# Astabile_Base.net
KiCad netlist of a schematic drawn in EAGLE
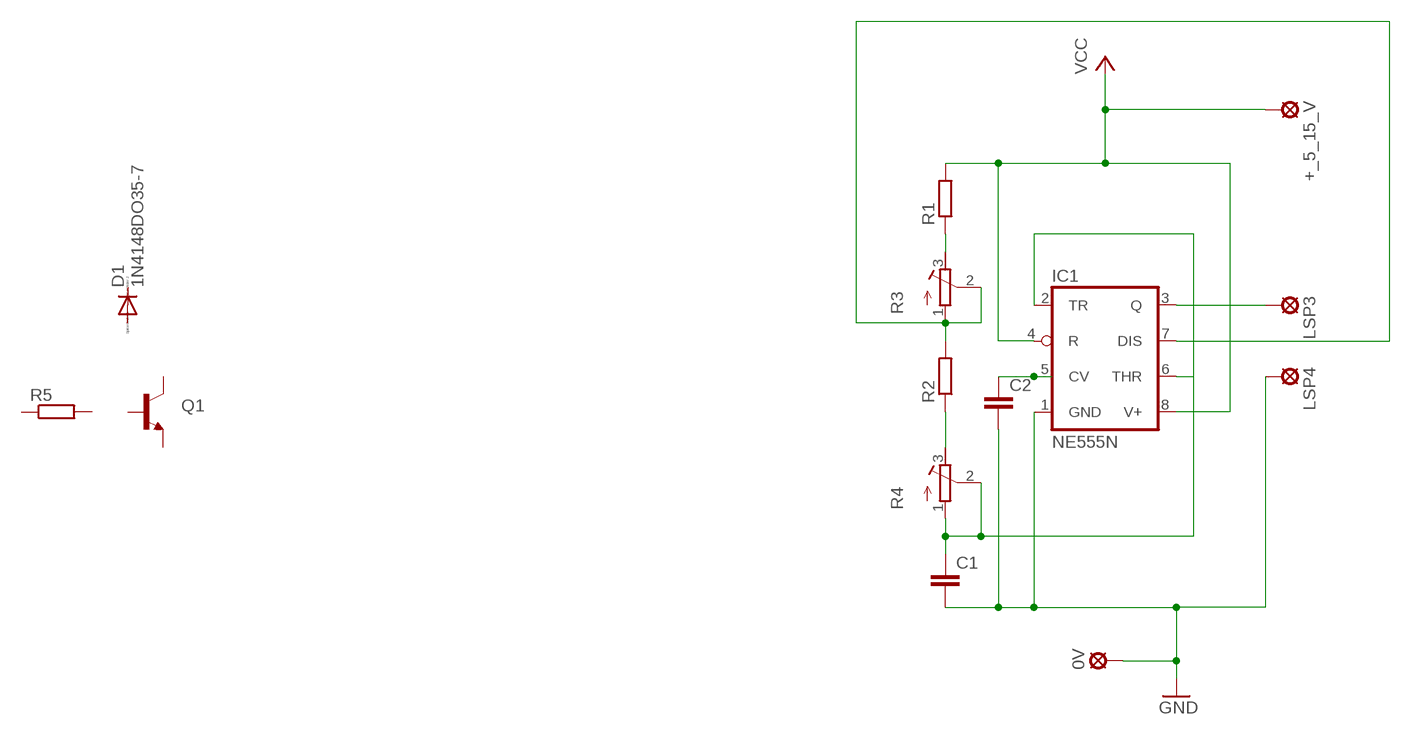
[diagram p0: schematic, sheet 1]

(export (version "E")
  (design (tool "Eeschema 10.0.6"))
  (components
    (comp (ref "+_5_15_V")
      (value "LSP10")
      (footprint "eagle-import:LSP10")
      (libsource (lib "eagle-import") (part "LSP10"))
    )
    (comp (ref "0V")
      (value "LSP10")
      (footprint "eagle-import:LSP10")
      (libsource (lib "eagle-import") (part "LSP10"))
    )
    (comp (ref "C1")
      (value "C-EU050-024X044")
      (footprint "eagle-import:C050-024X044")
      (libsource (lib "eagle-import") (part "C-EU050-024X044"))
    )
    (comp (ref "C2")
      (value "C-EU050-024X044")
      (footprint "eagle-import:C050-024X044")
      (libsource (lib "eagle-import") (part "C-EU050-024X044"))
    )
    (comp (ref "D1")
      (value "1N4148DO35-7")
      (footprint "eagle-import:DO35-7")
      (libsource (lib "eagle-import") (part "1N4148DO35-7"))
    )
    (comp (ref "IC1")
      (value "NE555N")
      (footprint "eagle-import:DIL08")
      (libsource (lib "eagle-import") (part "555NNE"))
    )
    (comp (ref "LSP3")
      (value "LSP10")
      (footprint "eagle-import:LSP10")
      (libsource (lib "eagle-import") (part "LSP10"))
    )
    (comp (ref "LSP4")
      (value "LSP10")
      (footprint "eagle-import:LSP10")
      (libsource (lib "eagle-import") (part "LSP10"))
    )
    (comp (ref "Q1")
      (value "TRANSISTOR_NPNBC547")
      (footprint "eagle-import:TO-92-AMMO")
      (libsource (lib "eagle-import") (part "TRANSISTOR_NPNBC547"))
    )
    (comp (ref "R1")
      (value "R-EU_0204/7")
      (footprint "eagle-import:0204_7")
      (libsource (lib "eagle-import") (part "R-EU_0204/7"))
    )
    (comp (ref "R2")
      (value "R-EU_0204/7")
      (footprint "eagle-import:0204_7")
      (libsource (lib "eagle-import") (part "R-EU_0204/7"))
    )
    (comp (ref "R3")
      (value "R-TRIMM3339P")
      (footprint "eagle-import:RTRIM3339P")
      (libsource (lib "eagle-import") (part "R-TRIMM3339P"))
    )
    (comp (ref "R4")
      (value "R-TRIMM3339P")
      (footprint "eagle-import:RTRIM3339P")
      (libsource (lib "eagle-import") (part "R-TRIMM3339P"))
    )
    (comp (ref "R5")
      (value "R-EU_0207/2V")
      (footprint "eagle-import:0207_2V")
      (libsource (lib "eagle-import") (part "R-EU_0207/2V"))
    )
  )
  (nets
    (net (code "1") (name "GND") (class "Default")
      (node (ref "0V") (pin "MP") (pinfunction "MP_MP") (pintype "passive"))
      (node (ref "C1") (pin "2") (pinfunction "2_2") (pintype "passive"))
      (node (ref "C2") (pin "2") (pinfunction "2_2") (pintype "passive"))
      (node (ref "IC1") (pin "1") (pinfunction "GND_1") (pintype "power_in"))
      (node (ref "LSP4") (pin "MP") (pinfunction "MP_MP") (pintype "passive"))
    )
    (net (code "2") (name "Net-(IC1-CV)") (class "Default")
      (node (ref "C2") (pin "1") (pinfunction "1_1") (pintype "passive"))
      (node (ref "IC1") (pin "5") (pinfunction "CV_5") (pintype "input"))
    )
    (net (code "3") (name "Net-(IC1-DIS)") (class "Default")
      (node (ref "IC1") (pin "7") (pinfunction "DIS_7") (pintype "input"))
      (node (ref "R2") (pin "2") (pinfunction "2_2") (pintype "passive"))
      (node (ref "R3") (pin "1") (pinfunction "A_1") (pintype "passive"))
      (node (ref "R3") (pin "2") (pinfunction "S_2") (pintype "passive"))
    )
    (net (code "4") (name "Net-(IC1-Q)") (class "Default")
      (node (ref "IC1") (pin "3") (pinfunction "Q_3") (pintype "output"))
      (node (ref "LSP3") (pin "MP") (pinfunction "MP_MP") (pintype "passive"))
    )
    (net (code "5") (name "Net-(IC1-THR)") (class "Default")
      (node (ref "C1") (pin "1") (pinfunction "1_1") (pintype "passive"))
      (node (ref "IC1") (pin "2") (pinfunction "TR_2") (pintype "input"))
      (node (ref "IC1") (pin "6") (pinfunction "THR_6") (pintype "input"))
      (node (ref "R4") (pin "1") (pinfunction "A_1") (pintype "passive"))
      (node (ref "R4") (pin "2") (pinfunction "S_2") (pintype "passive"))
    )
    (net (code "6") (name "Net-(R3-E)") (class "Default")
      (node (ref "R1") (pin "1") (pinfunction "1_1") (pintype "passive"))
      (node (ref "R3") (pin "3") (pinfunction "E_3") (pintype "passive"))
    )
    (net (code "7") (name "Net-(R4-E)") (class "Default")
      (node (ref "R2") (pin "1") (pinfunction "1_1") (pintype "passive"))
      (node (ref "R4") (pin "3") (pinfunction "E_3") (pintype "passive"))
    )
    (net (code "8") (name "VCC") (class "Default")
      (node (ref "+_5_15_V") (pin "MP") (pinfunction "MP_MP") (pintype "passive"))
      (node (ref "IC1") (pin "4") (pinfunction "R_4") (pintype "input"))
      (node (ref "IC1") (pin "8") (pinfunction "V+_8") (pintype "power_in"))
      (node (ref "R1") (pin "2") (pinfunction "2_2") (pintype "passive"))
    )
    (net (code "9") (name "unconnected-(D1-PadA)") (class "Default")
      (node (ref "D1") (pin "A") (pinfunction "A_A") (pintype "passive"))
    )
    (net (code "10") (name "unconnected-(D1-PadC)") (class "Default")
      (node (ref "D1") (pin "C") (pinfunction "C_C") (pintype "passive"))
    )
    (net (code "11") (name "unconnected-(Q1-B-Pad2)") (class "Default")
      (node (ref "Q1") (pin "2") (pinfunction "B_2") (pintype "passive"))
    )
    (net (code "12") (name "unconnected-(Q1-C-Pad1)") (class "Default")
      (node (ref "Q1") (pin "1") (pinfunction "C_1") (pintype "passive"))
    )
    (net (code "13") (name "unconnected-(Q1-E-Pad3)") (class "Default")
      (node (ref "Q1") (pin "3") (pinfunction "E_3") (pintype "passive"))
    )
    (net (code "14") (name "unconnected-(R5-Pad1)") (class "Default")
      (node (ref "R5") (pin "1") (pinfunction "1_1") (pintype "passive"))
    )
    (net (code "15") (name "unconnected-(R5-Pad2)") (class "Default")
      (node (ref "R5") (pin "2") (pinfunction "2_2") (pintype "passive"))
    )
  )
)
